# shem.net
KiCad netlist of a schematic drawn in EAGLE
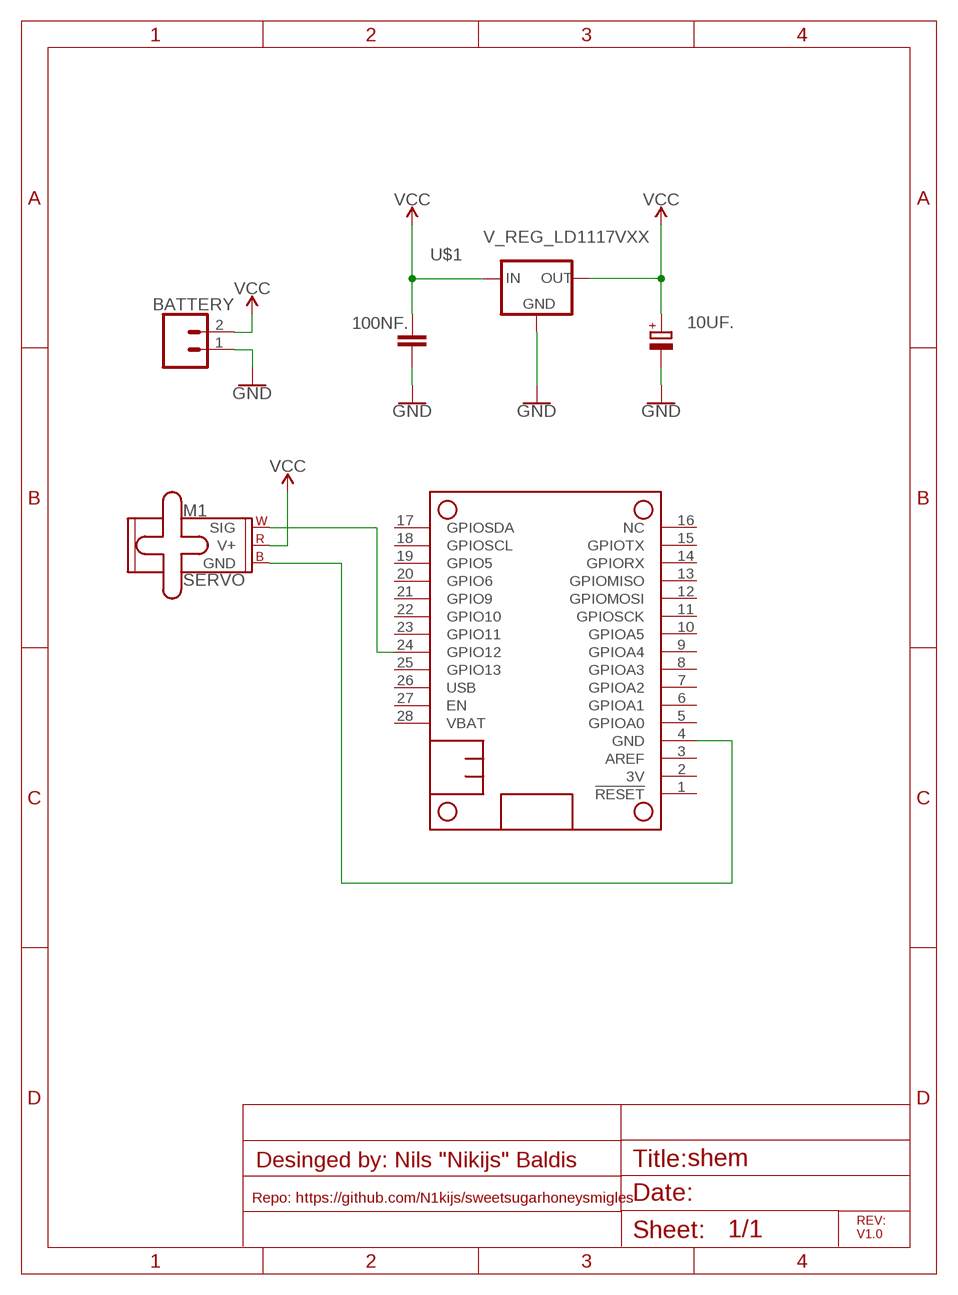
[diagram p0: schematic, sheet 1]

(export (version "E")
  (design (tool "Eeschema 10.0.6"))
  (components
    (comp (ref "10UF.")
      (value "CPOL-EUE1.8-4")
      (footprint "eagle-import:E1,8-4")
      (libsource (lib "eagle-import") (part "CPOL-EUE1.8-4"))
    )
    (comp (ref "100NF.")
      (value "C-EU025-025X050")
      (footprint "eagle-import:C025-025X050")
      (libsource (lib "eagle-import") (part "C-EU025-025X050"))
    )
    (comp (ref "BATTERY")
      (value "M02")
      (footprint "eagle-import:02P")
      (libsource (lib "eagle-import") (part "M02"))
    )
    (comp (ref "M1")
      (value "SERVO")
      (footprint "eagle-import:1X03")
      (libsource (lib "eagle-import") (part "SERVO"))
    )
    (comp (ref "MS1")
      (value "FEATHERWING")
      (footprint "eagle-import:FEATHERWING")
      (libsource (lib "eagle-import") (part "FEATHERWING"))
    )
    (comp (ref "U$1")
      (value "V_REG_LD1117VXX")
      (footprint "eagle-import:78XXL")
      (libsource (lib "eagle-import") (part "V_REG_LD1117VXX"))
    )
  )
  (nets
    (net (code "1") (name "/3V") (class "Default")
      (node (ref "MS1") (pin "2") (pinfunction "3V_2") (pintype "power_in"))
    )
    (net (code "2") (name "/USB") (class "Default")
      (node (ref "MS1") (pin "26") (pinfunction "USB_26") (pintype "power_in"))
    )
    (net (code "3") (name "/VBAT") (class "Default")
      (node (ref "MS1") (pin "28") (pinfunction "VBAT_28") (pintype "power_in"))
    )
    (net (code "4") (name "GND") (class "Default")
      (node (ref "100NF.") (pin "2") (pinfunction "2_2") (pintype "passive"))
      (node (ref "10UF.") (pin "-") (pinfunction "-_-") (pintype "passive"))
      (node (ref "BATTERY") (pin "1") (pinfunction "1_1") (pintype "passive"))
      (node (ref "U$1") (pin "IN") (pinfunction "GND_IN") (pintype "input"))
    )
    (net (code "5") (name "Net-(M1-GND)") (class "Default")
      (node (ref "M1") (pin "3") (pinfunction "GND_3") (pintype "bidirectional"))
      (node (ref "MS1") (pin "4") (pinfunction "GND_4") (pintype "power_in"))
    )
    (net (code "6") (name "Net-(M1-SIG)") (class "Default")
      (node (ref "M1") (pin "1") (pinfunction "SIG_1") (pintype "bidirectional"))
      (node (ref "MS1") (pin "24") (pinfunction "GPIO12_24") (pintype "bidirectional"))
    )
    (net (code "7") (name "VCC") (class "Default")
      (node (ref "100NF.") (pin "1") (pinfunction "1_1") (pintype "passive"))
      (node (ref "10UF.") (pin "+") (pinfunction "+_+") (pintype "passive"))
      (node (ref "BATTERY") (pin "2") (pinfunction "2_2") (pintype "passive"))
      (node (ref "M1") (pin "2") (pinfunction "V+_2") (pintype "bidirectional"))
      (node (ref "U$1") (pin "GND") (pinfunction "OUT_GND") (pintype "passive"))
      (node (ref "U$1") (pin "OUT") (pinfunction "IN_OUT") (pintype "input"))
    )
    (net (code "8") (name "unconnected-(MS1-AREF-Pad3)") (class "Default")
      (node (ref "MS1") (pin "3") (pinfunction "AREF_3") (pintype "passive"))
    )
    (net (code "9") (name "unconnected-(MS1-EN-Pad27)") (class "Default")
      (node (ref "MS1") (pin "27") (pinfunction "EN_27") (pintype "passive"))
    )
    (net (code "10") (name "unconnected-(MS1-GPIO5-Pad19)") (class "Default")
      (node (ref "MS1") (pin "19") (pinfunction "GPIO5_19") (pintype "bidirectional"))
    )
    (net (code "11") (name "unconnected-(MS1-GPIO6-Pad20)") (class "Default")
      (node (ref "MS1") (pin "20") (pinfunction "GPIO6_20") (pintype "bidirectional"))
    )
    (net (code "12") (name "unconnected-(MS1-GPIO9-Pad21)") (class "Default")
      (node (ref "MS1") (pin "21") (pinfunction "GPIO9_21") (pintype "bidirectional"))
    )
    (net (code "13") (name "unconnected-(MS1-GPIO10-Pad22)") (class "Default")
      (node (ref "MS1") (pin "22") (pinfunction "GPIO10_22") (pintype "bidirectional"))
    )
    (net (code "14") (name "unconnected-(MS1-GPIO11-Pad23)") (class "Default")
      (node (ref "MS1") (pin "23") (pinfunction "GPIO11_23") (pintype "bidirectional"))
    )
    (net (code "15") (name "unconnected-(MS1-GPIO13-Pad25)") (class "Default")
      (node (ref "MS1") (pin "25") (pinfunction "GPIO13_25") (pintype "bidirectional"))
    )
    (net (code "16") (name "unconnected-(MS1-GPIOA0-Pad5)") (class "Default")
      (node (ref "MS1") (pin "5") (pinfunction "GPIOA0_5") (pintype "bidirectional"))
    )
    (net (code "17") (name "unconnected-(MS1-GPIOA1-Pad6)") (class "Default")
      (node (ref "MS1") (pin "6") (pinfunction "GPIOA1_6") (pintype "bidirectional"))
    )
    (net (code "18") (name "unconnected-(MS1-GPIOA2-Pad7)") (class "Default")
      (node (ref "MS1") (pin "7") (pinfunction "GPIOA2_7") (pintype "bidirectional"))
    )
    (net (code "19") (name "unconnected-(MS1-GPIOA3-Pad8)") (class "Default")
      (node (ref "MS1") (pin "8") (pinfunction "GPIOA3_8") (pintype "bidirectional"))
    )
    (net (code "20") (name "unconnected-(MS1-GPIOA4-Pad9)") (class "Default")
      (node (ref "MS1") (pin "9") (pinfunction "GPIOA4_9") (pintype "bidirectional"))
    )
    (net (code "21") (name "unconnected-(MS1-GPIOA5-Pad10)") (class "Default")
      (node (ref "MS1") (pin "10") (pinfunction "GPIOA5_10") (pintype "bidirectional"))
    )
    (net (code "22") (name "unconnected-(MS1-GPIOMISO-Pad13)") (class "Default")
      (node (ref "MS1") (pin "13") (pinfunction "GPIOMISO_13") (pintype "bidirectional"))
    )
    (net (code "23") (name "unconnected-(MS1-GPIOMOSI-Pad12)") (class "Default")
      (node (ref "MS1") (pin "12") (pinfunction "GPIOMOSI_12") (pintype "bidirectional"))
    )
    (net (code "24") (name "unconnected-(MS1-GPIORX-Pad14)") (class "Default")
      (node (ref "MS1") (pin "14") (pinfunction "GPIORX_14") (pintype "bidirectional"))
    )
    (net (code "25") (name "unconnected-(MS1-GPIOSCK-Pad11)") (class "Default")
      (node (ref "MS1") (pin "11") (pinfunction "GPIOSCK_11") (pintype "bidirectional"))
    )
    (net (code "26") (name "unconnected-(MS1-GPIOSCL-Pad18)") (class "Default")
      (node (ref "MS1") (pin "18") (pinfunction "GPIOSCL_18") (pintype "bidirectional"))
    )
    (net (code "27") (name "unconnected-(MS1-GPIOSDA-Pad17)") (class "Default")
      (node (ref "MS1") (pin "17") (pinfunction "GPIOSDA_17") (pintype "bidirectional"))
    )
    (net (code "28") (name "unconnected-(MS1-GPIOTX-Pad15)") (class "Default")
      (node (ref "MS1") (pin "15") (pinfunction "GPIOTX_15") (pintype "bidirectional"))
    )
    (net (code "29") (name "unconnected-(MS1-NC-Pad16)") (class "Default")
      (node (ref "MS1") (pin "16") (pinfunction "NC_16") (pintype "passive"))
    )
    (net (code "30") (name "unconnected-(MS1-~{RESET}-Pad1)") (class "Default")
      (node (ref "MS1") (pin "1") (pinfunction "~{RESET}_1") (pintype "input"))
    )
  )
)
